# PD_MK2_Power.net
KiCad netlist of a schematic drawn in Altium Designer
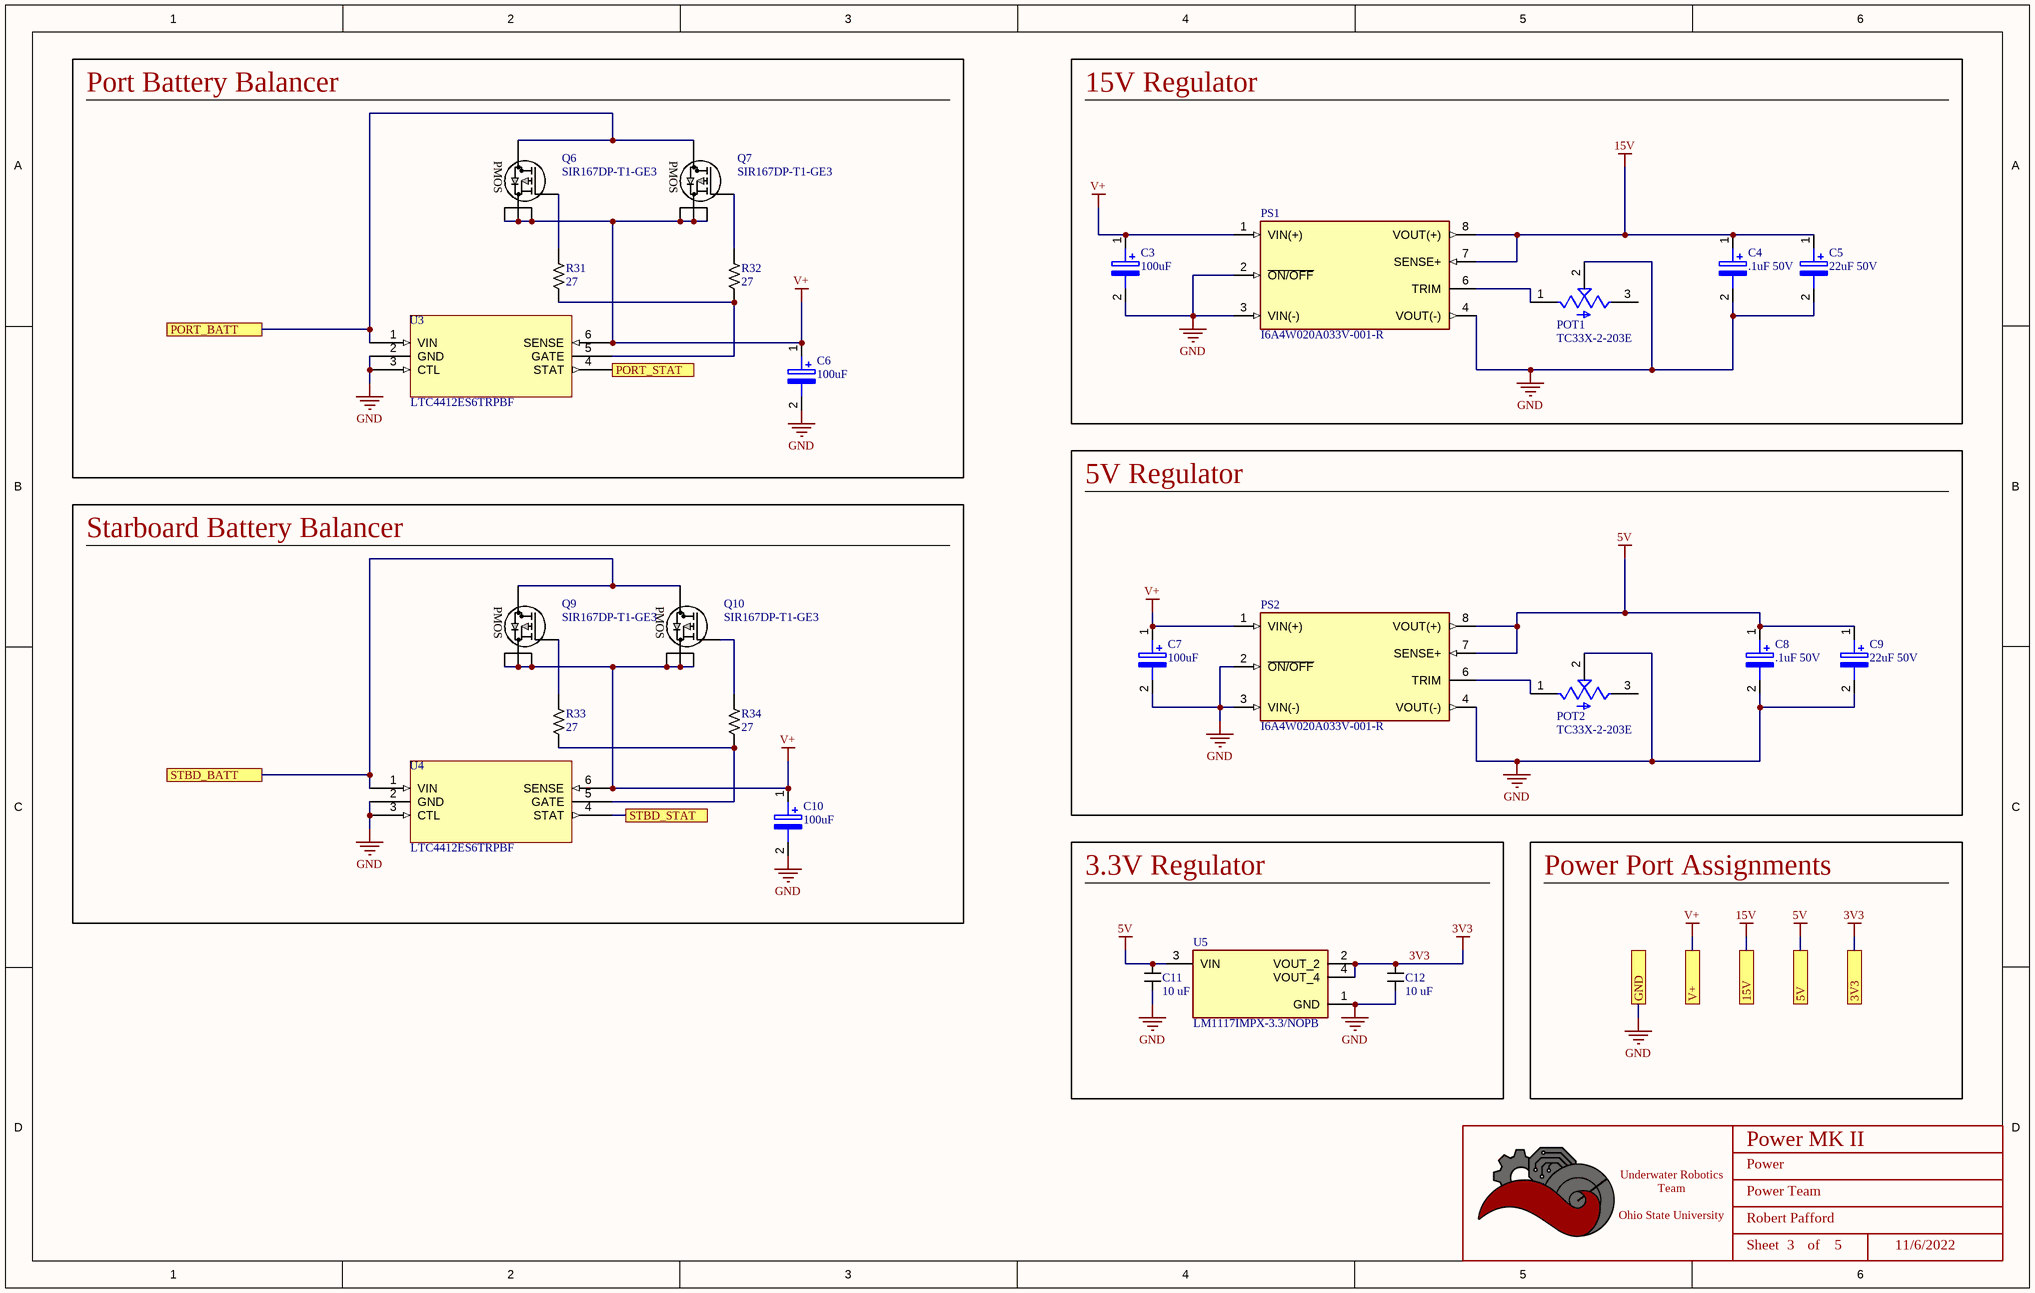
[diagram p0: PD_MK2_Power.SchDoc]

(export (version "E")
  (design (tool "Eeschema 10.0.6"))
  (components
    (comp (ref "C3")
      (value "100uF")
      (footprint "CAPAE430X550N")
      (description "4.7ÂµF 16V Aluminum Electrolytic Capacitors Radial, Can - SMD 2000 Hrs @ 85Â°C")
      (fields (field (name "MP") "865250340002") (field (name "MF") "Wurth Elektronik"))
      (libsource (lib "865250340002") (part "865250340002"))
    )
    (comp (ref "C4")
      (value ".1uF 50V")
      (footprint "CAPAE430X550N")
      (description "0.1礔 50V Aluminum Electrolytic Capacitors Radial, Can - SMD 2000 Hrs @ 85掳C")
      (fields (field (name "MP") "865250340002") (field (name "MF") "Wurth Elektronik"))
      (libsource (lib "865250340002") (part "865250340002"))
    )
    (comp (ref "C5")
      (value "22uF 50V")
      (footprint "CAPAE430X550N")
      (description "4.7ÂµF 16V Aluminum Electrolytic Capacitors Radial, Can - SMD 2000 Hrs @ 85Â°C")
      (fields (field (name "MP") "865250340002") (field (name "MF") "Wurth Elektronik"))
      (libsource (lib "865250340002") (part "865250340002"))
    )
    (comp (ref "C6")
      (value "100uF")
      (footprint "CAPAE430X550N")
      (description "4.7ÂµF 16V Aluminum Electrolytic Capacitors Radial, Can - SMD 2000 Hrs @ 85Â°C")
      (fields (field (name "MP") "865250340002") (field (name "MF") "Wurth Elektronik"))
      (libsource (lib "865250340002") (part "865250340002"))
    )
    (comp (ref "C7")
      (value "100uF")
      (footprint "CAPAE430X550N")
      (description "4.7ÂµF 16V Aluminum Electrolytic Capacitors Radial, Can - SMD 2000 Hrs @ 85Â°C")
      (fields (field (name "MP") "865250340002") (field (name "MF") "Wurth Elektronik"))
      (libsource (lib "865250340002") (part "865250340002"))
    )
    (comp (ref "C8")
      (value ".1uF 50V")
      (footprint "CAPAE430X550N")
      (description "4.7ÂµF 16V Aluminum Electrolytic Capacitors Radial, Can - SMD 2000 Hrs @ 85Â°C")
      (fields (field (name "MP") "865250340002") (field (name "MF") "Wurth Elektronik"))
      (libsource (lib "865250340002") (part "865250340002"))
    )
    (comp (ref "C9")
      (value "22uF 50V")
      (footprint "CAPAE430X550N")
      (description "4.7ÂµF 16V Aluminum Electrolytic Capacitors Radial, Can - SMD 2000 Hrs @ 85Â°C")
      (fields (field (name "MP") "865250340002") (field (name "MF") "Wurth Elektronik"))
      (libsource (lib "865250340002") (part "865250340002"))
    )
    (comp (ref "C10")
      (value "100uF")
      (footprint "CAPAE430X550N")
      (description "4.7ÂµF 16V Aluminum Electrolytic Capacitors Radial, Can - SMD 2000 Hrs @ 85Â°C")
      (fields (field (name "MP") "865250340002") (field (name "MF") "Wurth Elektronik"))
      (libsource (lib "865250340002") (part "865250340002"))
    )
    (comp (ref "C11")
      (value "10uF Ceramic 6.3V")
      (footprint "CAPACITOR_0603")
      (description "Cap 10uF 6.3V +/-20%\r\nCeramic 0603")
      (fields
        (field (name "TOLERANCE") "+/- 20%")
        (field (name "VOLTAGE") "6.3V")
        (field (name "VALUE (UF)") "10 uF")
        (field (name "MADE BY") "Flip B")
      )
      (libsource (lib "Capacitors") (part "CAPACITOR_10uF_0603"))
    )
    (comp (ref "C12")
      (value "10uF Ceramic 6.3V")
      (footprint "CAPACITOR_0603")
      (description "Cap 10uF 6.3V +/-20%\r\nCeramic 0603")
      (fields
        (field (name "TOLERANCE") "+/- 20%")
        (field (name "VOLTAGE") "6.3V")
        (field (name "VALUE (UF)") "10 uF")
        (field (name "MADE BY") "Flip B")
      )
      (libsource (lib "Capacitors") (part "CAPACITOR_10uF_0603"))
    )
    (comp (ref "POT1")
      (value "TC33X-2-203E")
      (footprint "TRIM_TC33X-2-203E")
      (description "20 kOhms 0.1W, 1/10W J Lead Surface Mount Trimmer Potentiometer Cermet 1 Turn Top Adjustment")
      (fields (field (name "MF") "Bourns") (field (name "DIGI-KEY_PART_NUMBER") "TC33X-2-203ECT-ND"))
      (libsource (lib "TC33X-2-203E") (part "TC33X-2-203E"))
    )
    (comp (ref "POT2")
      (value "TC33X-2-203E")
      (footprint "TRIM_TC33X-2-203E")
      (description "20 kOhms 0.1W, 1/10W J Lead Surface Mount Trimmer Potentiometer Cermet 1 Turn Top Adjustment")
      (fields (field (name "MF") "Bourns") (field (name "DIGI-KEY_PART_NUMBER") "TC33X-2-203ECT-ND"))
      (libsource (lib "TC33X-2-203E") (part "TC33X-2-203E"))
    )
    (comp (ref "PS1")
      (value "I6A4W020A033V-001-R")
      (footprint "CONV_I6A4W020A033V-001-R")
      (description "Non-Isolated PoL Module DC DC Converter 1 Output 3.3 ~ 15V 20A 9V - 53V Input")
      (fields (field (name "MF") "TDK-Lambda Americas"))
      (libsource (lib "I6A4W020A033V-001-R") (part "I6A4W020A033V-001-R"))
    )
    (comp (ref "PS2")
      (value "I6A4W020A033V-001-R")
      (footprint "CONV_I6A4W020A033V-001-R")
      (description "Non-Isolated PoL Module DC DC Converter 1 Output 3.3 ~ 15V 20A 9V - 53V Input")
      (fields (field (name "MF") "TDK-Lambda Americas"))
      (libsource (lib "I6A4W020A033V-001-R") (part "I6A4W020A033V-001-R"))
    )
    (comp (ref "Q6")
      (value "SIR167DP-T1-GE3")
      (footprint "MOSFET_7DP-T1-GE3_VIS")
      (description "P-Channel 30 V 60A (Tc) 65.8W (Tc) Surface Mount PowerPAK® SO-8")
      (fields (field (name "COPYRIGHT") "Copyright (C) 2022 Ultra Librarian. All rights reserved."))
      (libsource (lib "Transistors") (part "SIR167DP-T1-GE3"))
    )
    (comp (ref "Q7")
      (value "SIR167DP-T1-GE3")
      (footprint "MOSFET_7DP-T1-GE3_VIS")
      (description "P-Channel 30 V 60A (Tc) 65.8W (Tc) Surface Mount PowerPAK® SO-8")
      (fields (field (name "COPYRIGHT") "Copyright (C) 2022 Ultra Librarian. All rights reserved."))
      (libsource (lib "Transistors") (part "SIR167DP-T1-GE3"))
    )
    (comp (ref "Q9")
      (value "SIR167DP-T1-GE3")
      (footprint "MOSFET_7DP-T1-GE3_VIS")
      (description "P-Channel 30 V 60A (Tc) 65.8W (Tc) Surface Mount PowerPAK® SO-8")
      (fields (field (name "COPYRIGHT") "Copyright (C) 2022 Ultra Librarian. All rights reserved."))
      (libsource (lib "Transistors") (part "SIR167DP-T1-GE3"))
    )
    (comp (ref "Q10")
      (value "SIR167DP-T1-GE3")
      (footprint "MOSFET_7DP-T1-GE3_VIS")
      (description "P-Channel 30 V 60A (Tc) 65.8W (Tc) Surface Mount PowerPAK® SO-8")
      (fields (field (name "COPYRIGHT") "Copyright (C) 2022 Ultra Librarian. All rights reserved."))
      (libsource (lib "Transistors") (part "SIR167DP-T1-GE3"))
    )
    (comp (ref "R31")
      (value "27 Ohm 5% 1/8W")
      (footprint "RESISTOR_0603")
      (description "RES 27 OHM 5% 1/8W 0603")
      (fields
        (field (name "TOLERANCE") "+/- 5%")
        (field (name "VALUE  (OHMS)") "27")
        (field (name "MADE BY") "Robert Pafford")
      )
      (libsource (lib "Resistors") (part "RESISTOR_27_0603"))
    )
    (comp (ref "R32")
      (value "27 Ohm 5% 1/8W")
      (footprint "RESISTOR_0603")
      (description "RES 27 OHM 5% 1/8W 0603")
      (fields
        (field (name "TOLERANCE") "+/- 5%")
        (field (name "VALUE  (OHMS)") "27")
        (field (name "MADE BY") "Robert Pafford")
      )
      (libsource (lib "Resistors") (part "RESISTOR_27_0603"))
    )
    (comp (ref "R33")
      (value "27 Ohm 5% 1/8W")
      (footprint "RESISTOR_0603")
      (description "RES 27 OHM 5% 1/8W 0603")
      (fields
        (field (name "TOLERANCE") "+/- 5%")
        (field (name "VALUE  (OHMS)") "27")
        (field (name "MADE BY") "Robert Pafford")
      )
      (libsource (lib "Resistors") (part "RESISTOR_27_0603"))
    )
    (comp (ref "R34")
      (value "27 Ohm 5% 1/8W")
      (footprint "RESISTOR_0603")
      (description "RES 27 OHM 5% 1/8W 0603")
      (fields
        (field (name "TOLERANCE") "+/- 5%")
        (field (name "VALUE  (OHMS)") "27")
        (field (name "MADE BY") "Robert Pafford")
      )
      (libsource (lib "Resistors") (part "RESISTOR_27_0603"))
    )
    (comp (ref "U3")
      (value "LTC4412ES6TRPBF")
      (footprint "TSOT-23_S6")
      (description "OR Controller Source Selector Switch P-Channel 2:1 TSOT-23-6")
      (fields (field (name "MP") "LTC4412ES6#TRPBF") (field (name "MF") "Analog Devices"))
      (libsource (lib "Integrated Circuits") (part "LTC4412ES6TRPBF"))
    )
    (comp (ref "U4")
      (value "LTC4412ES6TRPBF")
      (footprint "TSOT-23_S6")
      (description "OR Controller Source Selector Switch P-Channel 2:1 TSOT-23-6")
      (fields (field (name "MP") "LTC4412ES6#TRPBF") (field (name "MF") "Analog Devices"))
      (libsource (lib "Integrated Circuits") (part "LTC4412ES6TRPBF"))
    )
    (comp (ref "U5")
      (value "LM1117IMPX-3.3/NOPB")
      (footprint "SOT-223-4")
      (description "800-mA 15-V linear voltage regulator 4-SOT-223 -40 to 125")
      (fields (field (name "MF") "Texas Instruments"))
      (libsource (lib "Integrated Circuits") (part "LM1117IMPX-3.3/NOPB"))
    )
  )
  (nets
    (net (code "1") (name "/PORT_BATT") (class "Default")
      (node (ref "Q6") (pin "D") (pinfunction "D_D") (pintype "passive"))
      (node (ref "Q7") (pin "D") (pinfunction "D_D") (pintype "passive"))
      (node (ref "U3") (pin "1") (pinfunction "VIN_1") (pintype "input"))
    )
    (net (code "2") (name "/PORT_STAT") (class "Default")
      (node (ref "U3") (pin "4") (pinfunction "STAT_4") (pintype "output"))
    )
    (net (code "3") (name "/STBD_BATT") (class "Default")
      (node (ref "Q10") (pin "D") (pinfunction "D_D") (pintype "passive"))
      (node (ref "Q9") (pin "D") (pinfunction "D_D") (pintype "passive"))
      (node (ref "U4") (pin "1") (pinfunction "VIN_1") (pintype "input"))
    )
    (net (code "4") (name "/STBD_STAT") (class "Default")
      (node (ref "U4") (pin "4") (pinfunction "STAT_4") (pintype "output"))
    )
    (net (code "5") (name "3V3") (class "Default")
      (node (ref "C12") (pin "1") (pinfunction "1_1") (pintype "passive"))
      (node (ref "U5") (pin "2") (pinfunction "VOUT_2_2") (pintype "power_in"))
      (node (ref "U5") (pin "4") (pinfunction "VOUT_4_4") (pintype "power_in"))
    )
    (net (code "6") (name "5V") (class "Default")
      (node (ref "C11") (pin "1") (pinfunction "1_1") (pintype "passive"))
      (node (ref "C8") (pin "1") (pinfunction "POS_1") (pintype "bidirectional"))
      (node (ref "C9") (pin "1") (pinfunction "POS_1") (pintype "bidirectional"))
      (node (ref "PS2") (pin "7") (pinfunction "SENSE+_7") (pintype "input"))
      (node (ref "PS2") (pin "8") (pinfunction "VOUT(+)_8") (pintype "output"))
      (node (ref "U5") (pin "3") (pinfunction "VIN_3") (pintype "power_in"))
    )
    (net (code "7") (name "15V") (class "Default")
      (node (ref "C4") (pin "1") (pinfunction "POS_1") (pintype "bidirectional"))
      (node (ref "C5") (pin "1") (pinfunction "POS_1") (pintype "bidirectional"))
      (node (ref "PS1") (pin "7") (pinfunction "SENSE+_7") (pintype "input"))
      (node (ref "PS1") (pin "8") (pinfunction "VOUT(+)_8") (pintype "output"))
    )
    (net (code "8") (name "GND") (class "Default")
      (node (ref "C10") (pin "2") (pinfunction "NEG_2") (pintype "bidirectional"))
      (node (ref "C11") (pin "2") (pinfunction "2_2") (pintype "passive"))
      (node (ref "C12") (pin "2") (pinfunction "2_2") (pintype "passive"))
      (node (ref "C3") (pin "2") (pinfunction "NEG_2") (pintype "bidirectional"))
      (node (ref "C4") (pin "2") (pinfunction "NEG_2") (pintype "bidirectional"))
      (node (ref "C5") (pin "2") (pinfunction "NEG_2") (pintype "bidirectional"))
      (node (ref "C6") (pin "2") (pinfunction "NEG_2") (pintype "bidirectional"))
      (node (ref "C7") (pin "2") (pinfunction "NEG_2") (pintype "bidirectional"))
      (node (ref "C8") (pin "2") (pinfunction "NEG_2") (pintype "bidirectional"))
      (node (ref "C9") (pin "2") (pinfunction "NEG_2") (pintype "bidirectional"))
      (node (ref "POT1") (pin "2") (pinfunction "W_2") (pintype "passive"))
      (node (ref "POT2") (pin "2") (pinfunction "W_2") (pintype "passive"))
      (node (ref "PS1") (pin "2") (pinfunction "~{ON/OFF}_2") (pintype "input"))
      (node (ref "PS1") (pin "3") (pinfunction "VIN(-)_3") (pintype "input"))
      (node (ref "PS1") (pin "4") (pinfunction "VOUT(-)_4") (pintype "output"))
      (node (ref "PS2") (pin "2") (pinfunction "~{ON/OFF}_2") (pintype "input"))
      (node (ref "PS2") (pin "3") (pinfunction "VIN(-)_3") (pintype "input"))
      (node (ref "PS2") (pin "4") (pinfunction "VOUT(-)_4") (pintype "output"))
      (node (ref "U3") (pin "2") (pinfunction "GND_2") (pintype "power_in"))
      (node (ref "U3") (pin "3") (pinfunction "CTL_3") (pintype "input"))
      (node (ref "U4") (pin "2") (pinfunction "GND_2") (pintype "power_in"))
      (node (ref "U4") (pin "3") (pinfunction "CTL_3") (pintype "input"))
      (node (ref "U5") (pin "1") (pinfunction "GND_1") (pintype "power_in"))
    )
    (net (code "9") (name "Net-(POT1-CCW)") (class "Default")
      (node (ref "POT1") (pin "1") (pinfunction "CCW_1") (pintype "passive"))
      (node (ref "PS1") (pin "6") (pinfunction "TRIM_6") (pintype "passive"))
    )
    (net (code "10") (name "Net-(POT2-CCW)") (class "Default")
      (node (ref "POT2") (pin "1") (pinfunction "CCW_1") (pintype "passive"))
      (node (ref "PS2") (pin "6") (pinfunction "TRIM_6") (pintype "passive"))
    )
    (net (code "11") (name "Net-(Q6-G)") (class "Default")
      (node (ref "Q6") (pin "4") (pinfunction "G_4") (pintype "passive"))
      (node (ref "R31") (pin "1") (pinfunction "1_1") (pintype "passive"))
    )
    (net (code "12") (name "Net-(Q7-G)") (class "Default")
      (node (ref "Q7") (pin "4") (pinfunction "G_4") (pintype "passive"))
      (node (ref "R32") (pin "1") (pinfunction "1_1") (pintype "passive"))
    )
    (net (code "13") (name "Net-(Q9-G)") (class "Default")
      (node (ref "Q9") (pin "4") (pinfunction "G_4") (pintype "passive"))
      (node (ref "R33") (pin "1") (pinfunction "1_1") (pintype "passive"))
    )
    (net (code "14") (name "Net-(Q10-G)") (class "Default")
      (node (ref "Q10") (pin "4") (pinfunction "G_4") (pintype "passive"))
      (node (ref "R34") (pin "1") (pinfunction "1_1") (pintype "passive"))
    )
    (net (code "15") (name "Net-(U3-GATE)") (class "Default")
      (node (ref "R31") (pin "2") (pinfunction "2_2") (pintype "passive"))
      (node (ref "R32") (pin "2") (pinfunction "2_2") (pintype "passive"))
      (node (ref "U3") (pin "5") (pinfunction "GATE_5") (pintype "passive"))
    )
    (net (code "16") (name "Net-(U4-GATE)") (class "Default")
      (node (ref "R33") (pin "2") (pinfunction "2_2") (pintype "passive"))
      (node (ref "R34") (pin "2") (pinfunction "2_2") (pintype "passive"))
      (node (ref "U4") (pin "5") (pinfunction "GATE_5") (pintype "passive"))
    )
    (net (code "17") (name "V+") (class "Default")
      (node (ref "C10") (pin "1") (pinfunction "POS_1") (pintype "bidirectional"))
      (node (ref "C3") (pin "1") (pinfunction "POS_1") (pintype "bidirectional"))
      (node (ref "C6") (pin "1") (pinfunction "POS_1") (pintype "bidirectional"))
      (node (ref "C7") (pin "1") (pinfunction "POS_1") (pintype "bidirectional"))
      (node (ref "PS1") (pin "1") (pinfunction "VIN(+)_1") (pintype "input"))
      (node (ref "PS2") (pin "1") (pinfunction "VIN(+)_1") (pintype "input"))
      (node (ref "Q10") (pin "1") (pinfunction "S_1") (pintype "passive"))
      (node (ref "Q10") (pin "2") (pinfunction "S_2") (pintype "passive"))
      (node (ref "Q10") (pin "3") (pinfunction "S_3") (pintype "passive"))
      (node (ref "Q6") (pin "1") (pinfunction "S_1") (pintype "passive"))
      (node (ref "Q6") (pin "2") (pinfunction "S_2") (pintype "passive"))
      (node (ref "Q6") (pin "3") (pinfunction "S_3") (pintype "passive"))
      (node (ref "Q7") (pin "1") (pinfunction "S_1") (pintype "passive"))
      (node (ref "Q7") (pin "2") (pinfunction "S_2") (pintype "passive"))
      (node (ref "Q7") (pin "3") (pinfunction "S_3") (pintype "passive"))
      (node (ref "Q9") (pin "1") (pinfunction "S_1") (pintype "passive"))
      (node (ref "Q9") (pin "2") (pinfunction "S_2") (pintype "passive"))
      (node (ref "Q9") (pin "3") (pinfunction "S_3") (pintype "passive"))
      (node (ref "U3") (pin "6") (pinfunction "SENSE_6") (pintype "input"))
      (node (ref "U4") (pin "6") (pinfunction "SENSE_6") (pintype "input"))
    )
    (net (code "18") (name "unconnected-(POT1-CW-Pad3)") (class "Default")
      (node (ref "POT1") (pin "3") (pinfunction "CW_3") (pintype "passive"))
    )
    (net (code "19") (name "unconnected-(POT2-CW-Pad3)") (class "Default")
      (node (ref "POT2") (pin "3") (pinfunction "CW_3") (pintype "passive"))
    )
  )
)
